# Digital_Port_F_Default_State_DIP.net
KiCad netlist of a schematic drawn in Altium Designer
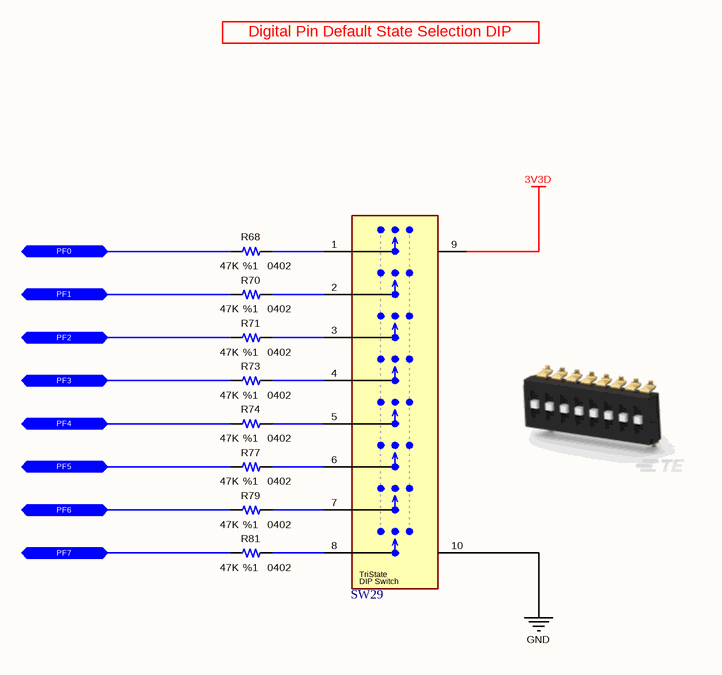
[diagram p0: Digital Port F Default State DIP.SchDoc]

(export (version "E")
  (design (tool "Eeschema 10.0.6"))
  (components
    (comp (ref "R68")
      (value "47K")
      (footprint "RESISTOR_0402")
      (description "Thick Film Resistors - SMD 1/16 W 47 Kohms 1%")
      (fields
        (field (name "MANUFACTURER PART NUMBER") "CRCW040247K0FKED")
        (field (name "MOUSER PART NUMBER") "71-CRCW0402-47K-E3")
        (field (name "TOLERANCE") "%1")
        (field (name "CASE") "0402")
      )
      (libsource (lib "Ovoo_Library") (part "Resistor - 47K"))
    )
    (comp (ref "R70")
      (value "47K")
      (footprint "RESISTOR_0402")
      (description "Thick Film Resistors - SMD 1/16 W 47 Kohms 1%")
      (fields
        (field (name "MANUFACTURER PART NUMBER") "CRCW040247K0FKED")
        (field (name "MOUSER PART NUMBER") "71-CRCW0402-47K-E3")
        (field (name "TOLERANCE") "%1")
        (field (name "CASE") "0402")
      )
      (libsource (lib "Ovoo_Library") (part "Resistor - 47K"))
    )
    (comp (ref "R71")
      (value "47K")
      (footprint "RESISTOR_0402")
      (description "Thick Film Resistors - SMD 1/16 W 47 Kohms 1%")
      (fields
        (field (name "MANUFACTURER PART NUMBER") "CRCW040247K0FKED")
        (field (name "MOUSER PART NUMBER") "71-CRCW0402-47K-E3")
        (field (name "TOLERANCE") "%1")
        (field (name "CASE") "0402")
      )
      (libsource (lib "Ovoo_Library") (part "Resistor - 47K"))
    )
    (comp (ref "R73")
      (value "47K")
      (footprint "RESISTOR_0402")
      (description "Thick Film Resistors - SMD 1/16 W 47 Kohms 1%")
      (fields
        (field (name "MANUFACTURER PART NUMBER") "CRCW040247K0FKED")
        (field (name "MOUSER PART NUMBER") "71-CRCW0402-47K-E3")
        (field (name "TOLERANCE") "%1")
        (field (name "CASE") "0402")
      )
      (libsource (lib "Ovoo_Library") (part "Resistor - 47K"))
    )
    (comp (ref "R74")
      (value "47K")
      (footprint "RESISTOR_0402")
      (description "Thick Film Resistors - SMD 1/16 W 47 Kohms 1%")
      (fields
        (field (name "MANUFACTURER PART NUMBER") "CRCW040247K0FKED")
        (field (name "MOUSER PART NUMBER") "71-CRCW0402-47K-E3")
        (field (name "TOLERANCE") "%1")
        (field (name "CASE") "0402")
      )
      (libsource (lib "Ovoo_Library") (part "Resistor - 47K"))
    )
    (comp (ref "R77")
      (value "47K")
      (footprint "RESISTOR_0402")
      (description "Thick Film Resistors - SMD 1/16 W 47 Kohms 1%")
      (fields
        (field (name "MANUFACTURER PART NUMBER") "CRCW040247K0FKED")
        (field (name "MOUSER PART NUMBER") "71-CRCW0402-47K-E3")
        (field (name "TOLERANCE") "%1")
        (field (name "CASE") "0402")
      )
      (libsource (lib "Ovoo_Library") (part "Resistor - 47K"))
    )
    (comp (ref "R79")
      (value "47K")
      (footprint "RESISTOR_0402")
      (description "Thick Film Resistors - SMD 1/16 W 47 Kohms 1%")
      (fields
        (field (name "MANUFACTURER PART NUMBER") "CRCW040247K0FKED")
        (field (name "MOUSER PART NUMBER") "71-CRCW0402-47K-E3")
        (field (name "TOLERANCE") "%1")
        (field (name "CASE") "0402")
      )
      (libsource (lib "Ovoo_Library") (part "Resistor - 47K"))
    )
    (comp (ref "R81")
      (value "47K")
      (footprint "RESISTOR_0402")
      (description "Thick Film Resistors - SMD 1/16 W 47 Kohms 1%")
      (fields
        (field (name "MANUFACTURER PART NUMBER") "CRCW040247K0FKED")
        (field (name "MOUSER PART NUMBER") "71-CRCW0402-47K-E3")
        (field (name "TOLERANCE") "%1")
        (field (name "CASE") "0402")
      )
      (libsource (lib "Ovoo_Library") (part "Resistor - 47K"))
    )
    (comp (ref "SW29")
      (value "DIP Switches/SIP Switches")
      (footprint "TDS08SGNNTR04")
      (description "DIP Switches/SIP Switches TRI-STATE DIP 8P G RAISED T&R")
      (fields
        (field (name "MANUFACTURER PART NUMBER") "TDS08SGNNTR04")
        (field (name "MOUSER PART NUMBER") "506-TDS08SGNNTR04")
      )
      (libsource (lib "Ovoo_Library") (part "Switch - DIP Switch (8 Pole TriState)"))
    )
  )
  (nets
    (net (code "1") (name "/PF0") (class "Default")
      (node (ref "R68") (pin "2") (pinfunction "2_2") (pintype "passive"))
    )
    (net (code "2") (name "/PF1") (class "Default")
      (node (ref "R70") (pin "2") (pinfunction "2_2") (pintype "passive"))
    )
    (net (code "3") (name "/PF2") (class "Default")
      (node (ref "R71") (pin "2") (pinfunction "2_2") (pintype "passive"))
    )
    (net (code "4") (name "/PF3") (class "Default")
      (node (ref "R73") (pin "2") (pinfunction "2_2") (pintype "passive"))
    )
    (net (code "5") (name "/PF4") (class "Default")
      (node (ref "R74") (pin "2") (pinfunction "2_2") (pintype "passive"))
    )
    (net (code "6") (name "/PF5") (class "Default")
      (node (ref "R77") (pin "2") (pinfunction "2_2") (pintype "passive"))
    )
    (net (code "7") (name "/PF6") (class "Default")
      (node (ref "R79") (pin "2") (pinfunction "2_2") (pintype "passive"))
    )
    (net (code "8") (name "/PF7") (class "Default")
      (node (ref "R81") (pin "2") (pinfunction "2_2") (pintype "passive"))
    )
    (net (code "9") (name "3V3D") (class "Default")
      (node (ref "SW29") (pin "9") (pinfunction "VCC_9") (pintype "passive"))
    )
    (net (code "10") (name "GND") (class "Default")
      (node (ref "SW29") (pin "10") (pinfunction "GND_10") (pintype "passive"))
    )
    (net (code "11") (name "Net-(R68-Pad1)") (class "Default")
      (node (ref "R68") (pin "1") (pinfunction "1_1") (pintype "passive"))
      (node (ref "SW29") (pin "1") (pinfunction "1_1") (pintype "passive"))
    )
    (net (code "12") (name "Net-(R70-Pad1)") (class "Default")
      (node (ref "R70") (pin "1") (pinfunction "1_1") (pintype "passive"))
      (node (ref "SW29") (pin "2") (pinfunction "2_2") (pintype "passive"))
    )
    (net (code "13") (name "Net-(R71-Pad1)") (class "Default")
      (node (ref "R71") (pin "1") (pinfunction "1_1") (pintype "passive"))
      (node (ref "SW29") (pin "3") (pinfunction "3_3") (pintype "passive"))
    )
    (net (code "14") (name "Net-(R73-Pad1)") (class "Default")
      (node (ref "R73") (pin "1") (pinfunction "1_1") (pintype "passive"))
      (node (ref "SW29") (pin "4") (pinfunction "4_4") (pintype "passive"))
    )
    (net (code "15") (name "Net-(R74-Pad1)") (class "Default")
      (node (ref "R74") (pin "1") (pinfunction "1_1") (pintype "passive"))
      (node (ref "SW29") (pin "5") (pinfunction "5_5") (pintype "passive"))
    )
    (net (code "16") (name "Net-(R77-Pad1)") (class "Default")
      (node (ref "R77") (pin "1") (pinfunction "1_1") (pintype "passive"))
      (node (ref "SW29") (pin "6") (pinfunction "6_6") (pintype "passive"))
    )
    (net (code "17") (name "Net-(R79-Pad1)") (class "Default")
      (node (ref "R79") (pin "1") (pinfunction "1_1") (pintype "passive"))
      (node (ref "SW29") (pin "7") (pinfunction "7_7") (pintype "passive"))
    )
    (net (code "18") (name "Net-(R81-Pad1)") (class "Default")
      (node (ref "R81") (pin "1") (pinfunction "1_1") (pintype "passive"))
      (node (ref "SW29") (pin "8") (pinfunction "8_8") (pintype "passive"))
    )
  )
)
